# eagle-APDS-9960.net
KiCad netlist of a schematic drawn in EAGLE
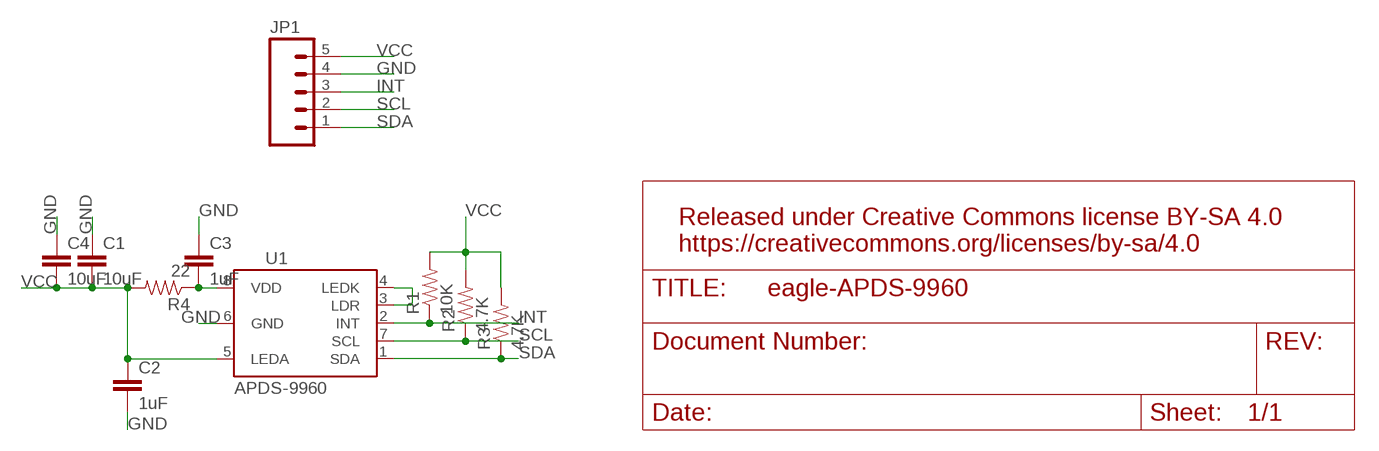
[diagram p0: schematic, sheet 1]

(export (version "E")
  (design (tool "Eeschema 10.0.6"))
  (components
    (comp (ref "C1")
      (value "10uF")
      (footprint "eagle-import:0805")
      (libsource (lib "eagle-import") (part "CAP0805"))
    )
    (comp (ref "C2")
      (value "1uF")
      (footprint "eagle-import:0805")
      (libsource (lib "eagle-import") (part "CAP0805"))
    )
    (comp (ref "C3")
      (value "1uF")
      (footprint "eagle-import:0805")
      (libsource (lib "eagle-import") (part "CAP0805"))
    )
    (comp (ref "C4")
      (value "10uF")
      (footprint "eagle-import:0805")
      (libsource (lib "eagle-import") (part "CAP0805"))
    )
    (comp (ref "JP1")
      (value "M05PTH")
      (footprint "eagle-import:1X05")
      (libsource (lib "eagle-import") (part "M05PTH"))
    )
    (comp (ref "R1")
      (value "10K")
      (footprint "eagle-import:0603-RES")
      (libsource (lib "eagle-import") (part "RESISTOR0603-RES"))
    )
    (comp (ref "R2")
      (value "4.7K")
      (footprint "eagle-import:0603-RES")
      (libsource (lib "eagle-import") (part "RESISTOR0603-RES"))
    )
    (comp (ref "R3")
      (value "4.7K")
      (footprint "eagle-import:0603-RES")
      (libsource (lib "eagle-import") (part "RESISTOR0603-RES"))
    )
    (comp (ref "R4")
      (value "22")
      (footprint "eagle-import:0603-RES")
      (libsource (lib "eagle-import") (part "RESISTOR0603-RES"))
    )
    (comp (ref "U1")
      (value "APDS-9960")
      (footprint "eagle-import:APDS-9960")
      (libsource (lib "eagle-import") (part "APDS-9960"))
    )
  )
  (nets
    (net (code "1") (name "/GND") (class "Default")
      (node (ref "C1") (pin "1") (pinfunction "1_1") (pintype "passive"))
      (node (ref "C2") (pin "2") (pinfunction "2_2") (pintype "passive"))
      (node (ref "C3") (pin "1") (pinfunction "1_1") (pintype "passive"))
      (node (ref "C4") (pin "1") (pinfunction "1_1") (pintype "passive"))
      (node (ref "JP1") (pin "4") (pinfunction "4_4") (pintype "passive"))
      (node (ref "U1") (pin "6") (pinfunction "GND_6") (pintype "bidirectional"))
    )
    (net (code "2") (name "/INT") (class "Default")
      (node (ref "JP1") (pin "3") (pinfunction "3_3") (pintype "passive"))
      (node (ref "R1") (pin "1") (pinfunction "1_1") (pintype "passive"))
      (node (ref "U1") (pin "2") (pinfunction "INT_2") (pintype "bidirectional"))
    )
    (net (code "3") (name "/SCL") (class "Default")
      (node (ref "JP1") (pin "2") (pinfunction "2_2") (pintype "passive"))
      (node (ref "R2") (pin "1") (pinfunction "1_1") (pintype "passive"))
      (node (ref "U1") (pin "7") (pinfunction "SCL_7") (pintype "bidirectional"))
    )
    (net (code "4") (name "/SDA") (class "Default")
      (node (ref "JP1") (pin "1") (pinfunction "1_1") (pintype "passive"))
      (node (ref "R3") (pin "1") (pinfunction "1_1") (pintype "passive"))
      (node (ref "U1") (pin "1") (pinfunction "SDA_1") (pintype "bidirectional"))
    )
    (net (code "5") (name "/VCC") (class "Default")
      (node (ref "C1") (pin "2") (pinfunction "2_2") (pintype "passive"))
      (node (ref "C2") (pin "1") (pinfunction "1_1") (pintype "passive"))
      (node (ref "C4") (pin "2") (pinfunction "2_2") (pintype "passive"))
      (node (ref "JP1") (pin "5") (pinfunction "5_5") (pintype "passive"))
      (node (ref "R1") (pin "2") (pinfunction "2_2") (pintype "passive"))
      (node (ref "R2") (pin "2") (pinfunction "2_2") (pintype "passive"))
      (node (ref "R3") (pin "2") (pinfunction "2_2") (pintype "passive"))
      (node (ref "R4") (pin "2") (pinfunction "2_2") (pintype "passive"))
      (node (ref "U1") (pin "5") (pinfunction "LEDA_5") (pintype "bidirectional"))
    )
    (net (code "6") (name "Net-(U1-LDR)") (class "Default")
      (node (ref "U1") (pin "3") (pinfunction "LDR_3") (pintype "bidirectional"))
      (node (ref "U1") (pin "4") (pinfunction "LEDK_4") (pintype "bidirectional"))
    )
    (net (code "7") (name "Net-(U1-VDD)") (class "Default")
      (node (ref "C3") (pin "2") (pinfunction "2_2") (pintype "passive"))
      (node (ref "R4") (pin "1") (pinfunction "1_1") (pintype "passive"))
      (node (ref "U1") (pin "8") (pinfunction "VDD_8") (pintype "bidirectional"))
    )
  )
)
